# Controllerv2.net
KiCad netlist of a schematic drawn in EAGLE
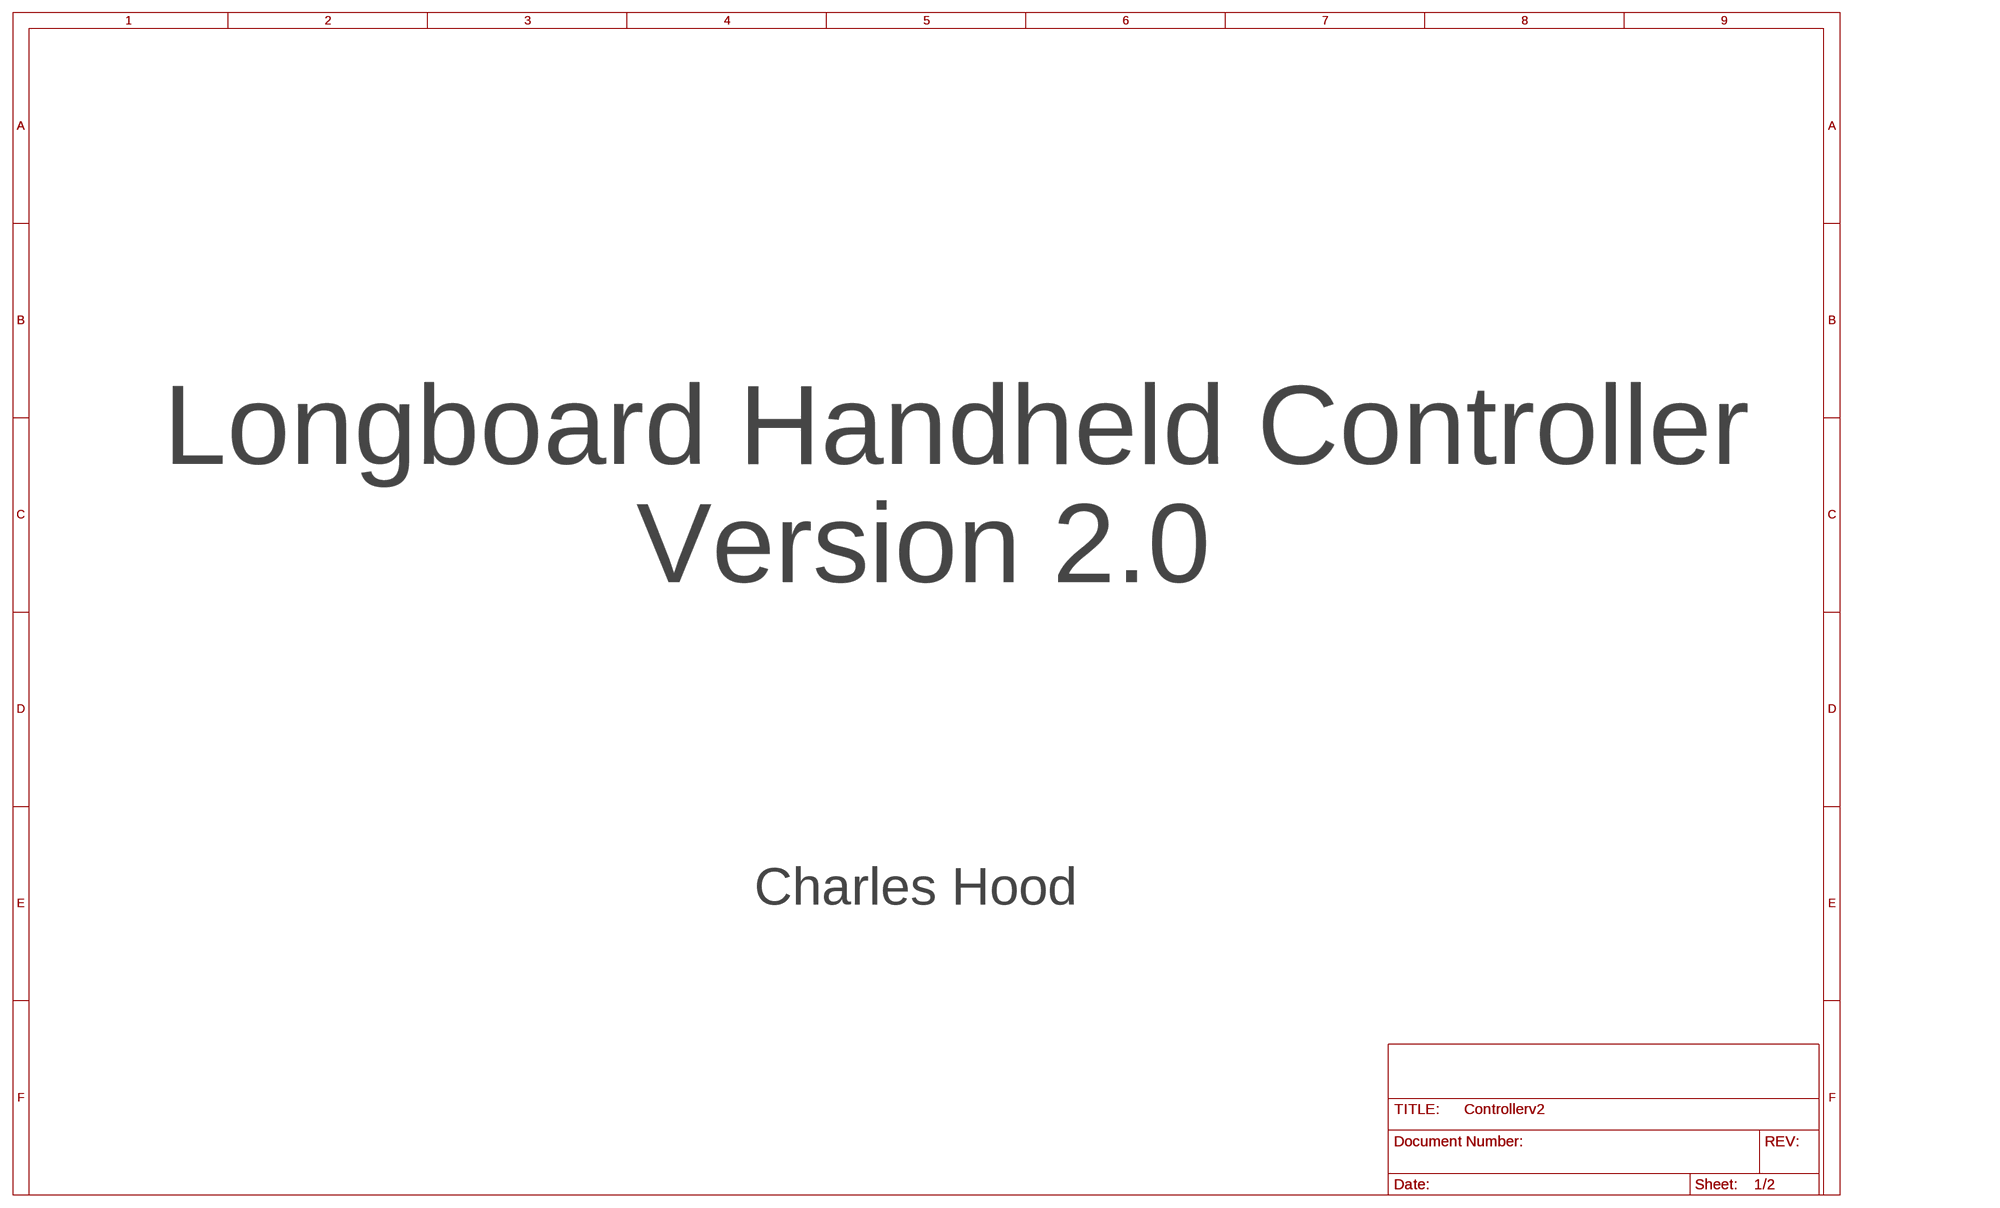
[diagram p0: schematic, sheet 1]
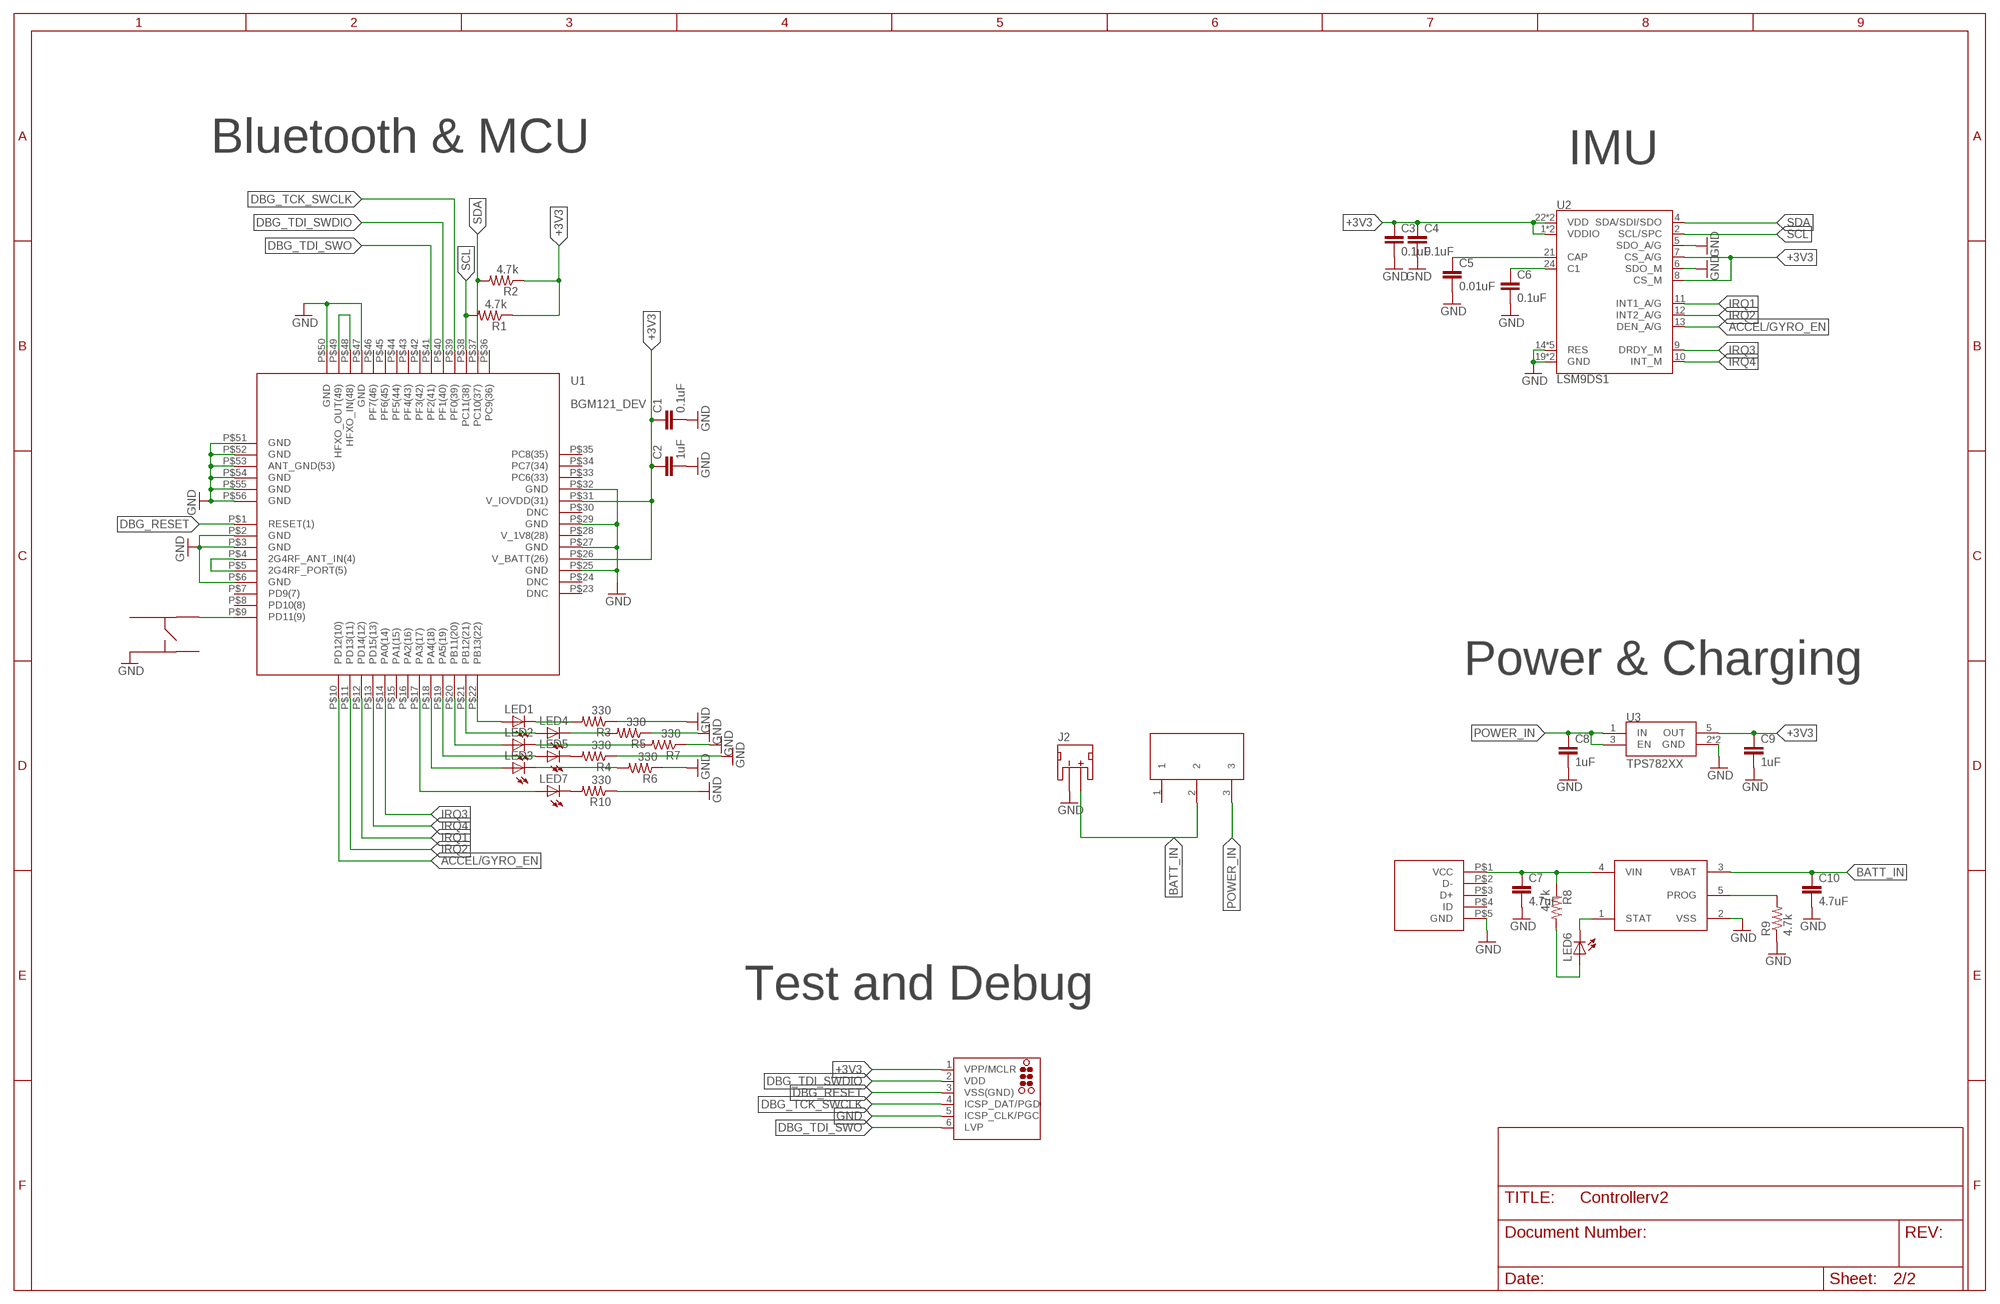
[diagram p1: schematic, sheet 2]

(export (version "E")
  (design (tool "Eeschema 10.0.6"))
  (components
    (comp (ref "C1")
      (value "0.1uF")
      (footprint "eagle-import:C0201")
      (libsource (lib "eagle-import") (part "C-EUC0201"))
    )
    (comp (ref "C2")
      (value "1uF")
      (footprint "eagle-import:C0201")
      (libsource (lib "eagle-import") (part "C-EUC0201"))
    )
    (comp (ref "C3")
      (value "0.1uF")
      (footprint "eagle-import:C0201")
      (libsource (lib "eagle-import") (part "C-EUC0201"))
    )
    (comp (ref "C4")
      (value "0.1uF")
      (footprint "eagle-import:C0201")
      (libsource (lib "eagle-import") (part "C-EUC0201"))
    )
    (comp (ref "C5")
      (value "0.01uF")
      (footprint "eagle-import:C0201")
      (libsource (lib "eagle-import") (part "C-EUC0201"))
    )
    (comp (ref "C6")
      (value "0.1uF")
      (footprint "eagle-import:C0201")
      (libsource (lib "eagle-import") (part "C-EUC0201"))
    )
    (comp (ref "C7")
      (value "4.7uF")
      (footprint "eagle-import:C0402")
      (libsource (lib "eagle-import") (part "C-EUC0402"))
    )
    (comp (ref "C8")
      (value "1uF")
      (footprint "eagle-import:C0201")
      (libsource (lib "eagle-import") (part "C-EUC0201"))
    )
    (comp (ref "C9")
      (value "1uF")
      (footprint "eagle-import:C0201")
      (libsource (lib "eagle-import") (part "C-EUC0201"))
    )
    (comp (ref "C10")
      (value "4.7uF")
      (footprint "eagle-import:C0402")
      (libsource (lib "eagle-import") (part "C-EUC0402"))
    )
    (comp (ref "J1")
      (value "MICRO_USB")
      (footprint "eagle-import:MOLEX_USB")
      (libsource (lib "eagle-import") (part "MICRO_USB"))
    )
    (comp (ref "J2")
      (value "JST_2MM_MALE")
      (footprint "eagle-import:JST-2-SMD")
      (libsource (lib "eagle-import") (part "JST_2MM_MALE"))
    )
    (comp (ref "J3")
      (value "TC2030-MCP-NL")
      (footprint "eagle-import:TC2030-MCP-NL")
      (libsource (lib "eagle-import") (part "TC2030-MCP-NL"))
    )
    (comp (ref "LED1")
      (value "LEDCHIP-LED0603")
      (footprint "eagle-import:CHIP-LED0603")
      (libsource (lib "eagle-import") (part "LEDCHIP-LED0603"))
    )
    (comp (ref "LED2")
      (value "LEDCHIP-LED0603")
      (footprint "eagle-import:CHIP-LED0603")
      (libsource (lib "eagle-import") (part "LEDCHIP-LED0603"))
    )
    (comp (ref "LED3")
      (value "LEDCHIP-LED0603")
      (footprint "eagle-import:CHIP-LED0603")
      (libsource (lib "eagle-import") (part "LEDCHIP-LED0603"))
    )
    (comp (ref "LED4")
      (value "LEDCHIP-LED0603")
      (footprint "eagle-import:CHIP-LED0603")
      (libsource (lib "eagle-import") (part "LEDCHIP-LED0603"))
    )
    (comp (ref "LED5")
      (value "LEDCHIP-LED0603")
      (footprint "eagle-import:CHIP-LED0603")
      (libsource (lib "eagle-import") (part "LEDCHIP-LED0603"))
    )
    (comp (ref "LED6")
      (value "LEDCHIP-LED0603")
      (footprint "eagle-import:CHIP-LED0603")
      (libsource (lib "eagle-import") (part "LEDCHIP-LED0603"))
    )
    (comp (ref "LED7")
      (value "LEDCHIP-LED0603")
      (footprint "eagle-import:CHIP-LED0603")
      (libsource (lib "eagle-import") (part "LEDCHIP-LED0603"))
    )
    (comp (ref "R1")
      (value "4.7k")
      (footprint "eagle-import:R0201")
      (libsource (lib "eagle-import") (part "R-US_R0201"))
    )
    (comp (ref "R2")
      (value "4.7k")
      (footprint "eagle-import:R0201")
      (libsource (lib "eagle-import") (part "R-US_R0201"))
    )
    (comp (ref "R3")
      (value "330")
      (footprint "eagle-import:R0201")
      (libsource (lib "eagle-import") (part "R-US_R0201"))
    )
    (comp (ref "R4")
      (value "330")
      (footprint "eagle-import:R0201")
      (libsource (lib "eagle-import") (part "R-US_R0201"))
    )
    (comp (ref "R5")
      (value "330")
      (footprint "eagle-import:R0201")
      (libsource (lib "eagle-import") (part "R-US_R0201"))
    )
    (comp (ref "R6")
      (value "330")
      (footprint "eagle-import:R0201")
      (libsource (lib "eagle-import") (part "R-US_R0201"))
    )
    (comp (ref "R7")
      (value "330")
      (footprint "eagle-import:R0201")
      (libsource (lib "eagle-import") (part "R-US_R0201"))
    )
    (comp (ref "R8")
      (value "4.7k")
      (footprint "eagle-import:R0201")
      (libsource (lib "eagle-import") (part "R-US_R0201"))
    )
    (comp (ref "R9")
      (value "4.7k")
      (footprint "eagle-import:R0201")
      (libsource (lib "eagle-import") (part "R-US_R0201"))
    )
    (comp (ref "R10")
      (value "330")
      (footprint "eagle-import:R0201")
      (libsource (lib "eagle-import") (part "R-US_R0201"))
    )
    (comp (ref "S1")
      (value "KMR731NG")
      (footprint "eagle-import:KMR731NG")
      (libsource (lib "eagle-import") (part "KMR731NG"))
    )
    (comp (ref "U$1")
      (value "SPDT_THRU")
      (footprint "eagle-import:SPDT_THRU")
      (libsource (lib "eagle-import") (part "SPDT_THRU"))
    )
    (comp (ref "U1")
      (value "BGM121_DEV")
      (footprint "eagle-import:BGM121_PAC")
      (libsource (lib "eagle-import") (part "BGM121_DEV"))
    )
    (comp (ref "U2")
      (value "LSM9DS1")
      (footprint "eagle-import:LGA24-8X4")
      (libsource (lib "eagle-import") (part "LSM9DS1"))
    )
    (comp (ref "U3")
      (value "TPS782XX")
      (footprint "eagle-import:SOT23-5L")
      (libsource (lib "eagle-import") (part "TPS782XX"))
    )
    (comp (ref "U4")
      (value "MCP73831")
      (footprint "eagle-import:SOT23-5L")
      (libsource (lib "eagle-import") (part "MCP73831"))
    )
  )
  (nets
    (net (code "1") (name "+3V3") (class "Default")
      (node (ref "C1") (pin "1") (pinfunction "1_1") (pintype "passive"))
      (node (ref "C2") (pin "1") (pinfunction "1_1") (pintype "passive"))
      (node (ref "C3") (pin "1") (pinfunction "1_1") (pintype "passive"))
      (node (ref "C4") (pin "1") (pinfunction "1_1") (pintype "passive"))
      (node (ref "C9") (pin "1") (pinfunction "1_1") (pintype "passive"))
      (node (ref "J3") (pin "1") (pinfunction "VPP/MCLR_1") (pintype "passive"))
      (node (ref "R1") (pin "1") (pinfunction "1_1") (pintype "passive"))
      (node (ref "R2") (pin "1") (pinfunction "1_1") (pintype "passive"))
      (node (ref "U1") (pin "P$26") (pinfunction "V_BATT(26)_P$26") (pintype "power_in"))
      (node (ref "U1") (pin "P$31") (pinfunction "V_IOVDD(31)_P$31") (pintype "power_in"))
      (node (ref "U2") (pin "1") (pinfunction "VDDIO_1") (pintype "bidirectional"))
      (node (ref "U2") (pin "22") (pinfunction "VDD_22") (pintype "bidirectional"))
      (node (ref "U2") (pin "23") (pinfunction "VDD_23") (pintype "bidirectional"))
      (node (ref "U2") (pin "3") (pinfunction "VDDIO_3") (pintype "bidirectional"))
      (node (ref "U2") (pin "7") (pinfunction "CS_A/G_7") (pintype "bidirectional"))
      (node (ref "U2") (pin "8") (pinfunction "CS_M_8") (pintype "bidirectional"))
      (node (ref "U3") (pin "5") (pinfunction "OUT_5") (pintype "bidirectional"))
    )
    (net (code "2") (name "ACCEL{slash}GYRO_EN") (class "Default")
      (node (ref "U1") (pin "P$10") (pinfunction "PD12(10)_P$10") (pintype "bidirectional"))
      (node (ref "U2") (pin "13") (pinfunction "DEN_A/G_13") (pintype "bidirectional"))
    )
    (net (code "3") (name "BATT_IN") (class "Default")
      (node (ref "C10") (pin "1") (pinfunction "1_1") (pintype "passive"))
      (node (ref "J2") (pin "2") (pinfunction "+_2") (pintype "bidirectional"))
      (node (ref "U$1") (pin "2") (pinfunction "2_2") (pintype "bidirectional"))
      (node (ref "U4") (pin "3") (pinfunction "VBAT_3") (pintype "bidirectional"))
    )
    (net (code "4") (name "DBG_RESET") (class "Default")
      (node (ref "J3") (pin "3") (pinfunction "VSS(GND)_3") (pintype "power_in"))
      (node (ref "U1") (pin "P$1") (pinfunction "RESET(1)_P$1") (pintype "input"))
    )
    (net (code "5") (name "DBG_TCK_SWCLK") (class "Default")
      (node (ref "J3") (pin "4") (pinfunction "ICSP_DAT/PGD_4") (pintype "bidirectional"))
      (node (ref "U1") (pin "P$39") (pinfunction "PF0(39)_P$39") (pintype "bidirectional"))
    )
    (net (code "6") (name "DBG_TDI_SWDIO") (class "Default")
      (node (ref "J3") (pin "2") (pinfunction "VDD_2") (pintype "power_in"))
      (node (ref "U1") (pin "P$40") (pinfunction "PF1(40)_P$40") (pintype "bidirectional"))
    )
    (net (code "7") (name "DBG_TDI_SWO") (class "Default")
      (node (ref "J3") (pin "6") (pinfunction "LVP_6") (pintype "bidirectional"))
      (node (ref "U1") (pin "P$41") (pinfunction "PF2(41)_P$41") (pintype "bidirectional"))
    )
    (net (code "8") (name "GND") (class "Default")
      (node (ref "C1") (pin "2") (pinfunction "2_2") (pintype "passive"))
      (node (ref "C10") (pin "2") (pinfunction "2_2") (pintype "passive"))
      (node (ref "C2") (pin "2") (pinfunction "2_2") (pintype "passive"))
      (node (ref "C3") (pin "2") (pinfunction "2_2") (pintype "passive"))
      (node (ref "C4") (pin "2") (pinfunction "2_2") (pintype "passive"))
      (node (ref "C5") (pin "2") (pinfunction "2_2") (pintype "passive"))
      (node (ref "C6") (pin "2") (pinfunction "2_2") (pintype "passive"))
      (node (ref "C7") (pin "2") (pinfunction "2_2") (pintype "passive"))
      (node (ref "C8") (pin "2") (pinfunction "2_2") (pintype "passive"))
      (node (ref "C9") (pin "2") (pinfunction "2_2") (pintype "passive"))
      (node (ref "J1") (pin "P$5") (pinfunction "GND_P$5") (pintype "bidirectional"))
      (node (ref "J2") (pin "1") (pinfunction "-_1") (pintype "bidirectional"))
      (node (ref "J3") (pin "5") (pinfunction "ICSP_CLK/PGC_5") (pintype "output"))
      (node (ref "R10") (pin "1") (pinfunction "1_1") (pintype "passive"))
      (node (ref "R3") (pin "1") (pinfunction "1_1") (pintype "passive"))
      (node (ref "R4") (pin "1") (pinfunction "1_1") (pintype "passive"))
      (node (ref "R5") (pin "1") (pinfunction "1_1") (pintype "passive"))
      (node (ref "R6") (pin "1") (pinfunction "1_1") (pintype "passive"))
      (node (ref "R7") (pin "1") (pinfunction "1_1") (pintype "passive"))
      (node (ref "R9") (pin "1") (pinfunction "1_1") (pintype "passive"))
      (node (ref "S1") (pin "P$4") (pinfunction "P$4_P$4") (pintype "bidirectional"))
      (node (ref "U1") (pin "P$2") (pinfunction "GND_P$2") (pintype "power_in"))
      (node (ref "U1") (pin "P$25") (pinfunction "GND_P$25") (pintype "power_in"))
      (node (ref "U1") (pin "P$27") (pinfunction "GND_P$27") (pintype "power_in"))
      (node (ref "U1") (pin "P$29") (pinfunction "GND_P$29") (pintype "power_in"))
      (node (ref "U1") (pin "P$3") (pinfunction "GND_P$3") (pintype "power_in"))
      (node (ref "U1") (pin "P$32") (pinfunction "GND_P$32") (pintype "power_in"))
      (node (ref "U1") (pin "P$47") (pinfunction "GND_P$47") (pintype "power_in"))
      (node (ref "U1") (pin "P$50") (pinfunction "GND_P$50") (pintype "power_in"))
      (node (ref "U1") (pin "P$51") (pinfunction "GND_P$51") (pintype "power_in"))
      (node (ref "U1") (pin "P$52") (pinfunction "GND_P$52") (pintype "power_in"))
      (node (ref "U1") (pin "P$53") (pinfunction "ANT_GND(53)_P$53") (pintype "power_in"))
      (node (ref "U1") (pin "P$54") (pinfunction "GND_P$54") (pintype "power_in"))
      (node (ref "U1") (pin "P$55") (pinfunction "GND_P$55") (pintype "power_in"))
      (node (ref "U1") (pin "P$56") (pinfunction "GND_P$56") (pintype "power_in"))
      (node (ref "U1") (pin "P$6") (pinfunction "GND_P$6") (pintype "power_in"))
      (node (ref "U2") (pin "14") (pinfunction "RES_14") (pintype "bidirectional"))
      (node (ref "U2") (pin "15") (pinfunction "RES_15") (pintype "bidirectional"))
      (node (ref "U2") (pin "16") (pinfunction "RES_16") (pintype "bidirectional"))
      (node (ref "U2") (pin "17") (pinfunction "RES_17") (pintype "bidirectional"))
      (node (ref "U2") (pin "18") (pinfunction "RES_18") (pintype "bidirectional"))
      (node (ref "U2") (pin "19") (pinfunction "GND_19") (pintype "bidirectional"))
      (node (ref "U2") (pin "20") (pinfunction "GND_20") (pintype "bidirectional"))
      (node (ref "U2") (pin "5") (pinfunction "SDO_A/G_5") (pintype "bidirectional"))
      (node (ref "U2") (pin "6") (pinfunction "SDO_M_6") (pintype "bidirectional"))
      (node (ref "U3") (pin "2") (pinfunction "GND_2") (pintype "bidirectional"))
      (node (ref "U3") (pin "4") (pinfunction "GND_4") (pintype "bidirectional"))
      (node (ref "U4") (pin "2") (pinfunction "VSS_2") (pintype "bidirectional"))
    )
    (net (code "9") (name "IRQ1") (class "Default")
      (node (ref "U1") (pin "P$12") (pinfunction "PD14(12)_P$12") (pintype "bidirectional"))
      (node (ref "U2") (pin "11") (pinfunction "INT1_A/G_11") (pintype "bidirectional"))
    )
    (net (code "10") (name "IRQ2") (class "Default")
      (node (ref "U1") (pin "P$11") (pinfunction "PD13(11)_P$11") (pintype "bidirectional"))
      (node (ref "U2") (pin "12") (pinfunction "INT2_A/G_12") (pintype "bidirectional"))
    )
    (net (code "11") (name "IRQ3") (class "Default")
      (node (ref "U1") (pin "P$14") (pinfunction "PA0(14)_P$14") (pintype "bidirectional"))
      (node (ref "U2") (pin "9") (pinfunction "DRDY_M_9") (pintype "bidirectional"))
    )
    (net (code "12") (name "IRQ4") (class "Default")
      (node (ref "U1") (pin "P$13") (pinfunction "PD15(13)_P$13") (pintype "bidirectional"))
      (node (ref "U2") (pin "10") (pinfunction "INT_M_10") (pintype "bidirectional"))
    )
    (net (code "13") (name "Net-(J1-VCC)") (class "Default")
      (node (ref "C7") (pin "1") (pinfunction "1_1") (pintype "passive"))
      (node (ref "J1") (pin "P$1") (pinfunction "VCC_P$1") (pintype "bidirectional"))
      (node (ref "R8") (pin "1") (pinfunction "1_1") (pintype "passive"))
      (node (ref "U4") (pin "4") (pinfunction "VIN_4") (pintype "bidirectional"))
    )
    (net (code "14") (name "Net-(LED1-PadC)") (class "Default")
      (node (ref "LED1") (pin "C") (pinfunction "C_C") (pintype "passive"))
      (node (ref "R3") (pin "2") (pinfunction "2_2") (pintype "passive"))
    )
    (net (code "15") (name "Net-(LED2-PadC)") (class "Default")
      (node (ref "LED2") (pin "C") (pinfunction "C_C") (pintype "passive"))
      (node (ref "R7") (pin "2") (pinfunction "2_2") (pintype "passive"))
    )
    (net (code "16") (name "Net-(LED3-PadC)") (class "Default")
      (node (ref "LED3") (pin "C") (pinfunction "C_C") (pintype "passive"))
      (node (ref "R6") (pin "2") (pinfunction "2_2") (pintype "passive"))
    )
    (net (code "17") (name "Net-(LED4-PadC)") (class "Default")
      (node (ref "LED4") (pin "C") (pinfunction "C_C") (pintype "passive"))
      (node (ref "R5") (pin "2") (pinfunction "2_2") (pintype "passive"))
    )
    (net (code "18") (name "Net-(LED5-PadC)") (class "Default")
      (node (ref "LED5") (pin "C") (pinfunction "C_C") (pintype "passive"))
      (node (ref "R4") (pin "2") (pinfunction "2_2") (pintype "passive"))
    )
    (net (code "19") (name "Net-(LED6-PadA)") (class "Default")
      (node (ref "LED6") (pin "A") (pinfunction "A_A") (pintype "passive"))
      (node (ref "R8") (pin "2") (pinfunction "2_2") (pintype "passive"))
    )
    (net (code "20") (name "Net-(LED7-PadC)") (class "Default")
      (node (ref "LED7") (pin "C") (pinfunction "C_C") (pintype "passive"))
      (node (ref "R10") (pin "2") (pinfunction "2_2") (pintype "passive"))
    )
    (net (code "21") (name "Net-(U1-2G4RF_ANT_IN(4))") (class "Default")
      (node (ref "U1") (pin "P$4") (pinfunction "2G4RF_ANT_IN(4)_P$4") (pintype "input"))
      (node (ref "U1") (pin "P$5") (pinfunction "2G4RF_PORT(5)_P$5") (pintype "input"))
    )
    (net (code "22") (name "Net-(U1-HFXO_IN(48))") (class "Default")
      (node (ref "U1") (pin "P$48") (pinfunction "HFXO_IN(48)_P$48") (pintype "input"))
      (node (ref "U1") (pin "P$49") (pinfunction "HFXO_OUT(49)_P$49") (pintype "output"))
    )
    (net (code "23") (name "Net-(U1-PA3(17))") (class "Default")
      (node (ref "LED7") (pin "A") (pinfunction "A_A") (pintype "passive"))
      (node (ref "U1") (pin "P$17") (pinfunction "PA3(17)_P$17") (pintype "bidirectional"))
    )
    (net (code "24") (name "Net-(U1-PA4(18))") (class "Default")
      (node (ref "LED3") (pin "A") (pinfunction "A_A") (pintype "passive"))
      (node (ref "U1") (pin "P$18") (pinfunction "PA4(18)_P$18") (pintype "bidirectional"))
    )
    (net (code "25") (name "Net-(U1-PA5(19))") (class "Default")
      (node (ref "LED5") (pin "A") (pinfunction "A_A") (pintype "passive"))
      (node (ref "U1") (pin "P$19") (pinfunction "PA5(19)_P$19") (pintype "bidirectional"))
    )
    (net (code "26") (name "Net-(U1-PB11(20))") (class "Default")
      (node (ref "LED2") (pin "A") (pinfunction "A_A") (pintype "passive"))
      (node (ref "U1") (pin "P$20") (pinfunction "PB11(20)_P$20") (pintype "bidirectional"))
    )
    (net (code "27") (name "Net-(U1-PB12(21))") (class "Default")
      (node (ref "LED4") (pin "A") (pinfunction "A_A") (pintype "passive"))
      (node (ref "U1") (pin "P$21") (pinfunction "PB12(21)_P$21") (pintype "bidirectional"))
    )
    (net (code "28") (name "Net-(U1-PB13(22))") (class "Default")
      (node (ref "LED1") (pin "A") (pinfunction "A_A") (pintype "passive"))
      (node (ref "U1") (pin "P$22") (pinfunction "PB13(22)_P$22") (pintype "bidirectional"))
    )
    (net (code "29") (name "Net-(U1-PD11(9))") (class "Default")
      (node (ref "S1") (pin "P$2") (pinfunction "P$2_P$2") (pintype "bidirectional"))
      (node (ref "U1") (pin "P$9") (pinfunction "PD11(9)_P$9") (pintype "bidirectional"))
    )
    (net (code "30") (name "Net-(U2-C1)") (class "Default")
      (node (ref "C6") (pin "1") (pinfunction "1_1") (pintype "passive"))
      (node (ref "U2") (pin "24") (pinfunction "C1_24") (pintype "bidirectional"))
    )
    (net (code "31") (name "Net-(U2-CAP)") (class "Default")
      (node (ref "C5") (pin "1") (pinfunction "1_1") (pintype "passive"))
      (node (ref "U2") (pin "21") (pinfunction "CAP_21") (pintype "bidirectional"))
    )
    (net (code "32") (name "Net-(U4-PROG)") (class "Default")
      (node (ref "R9") (pin "2") (pinfunction "2_2") (pintype "passive"))
      (node (ref "U4") (pin "5") (pinfunction "PROG_5") (pintype "bidirectional"))
    )
    (net (code "33") (name "Net-(U4-STAT)") (class "Default")
      (node (ref "LED6") (pin "C") (pinfunction "C_C") (pintype "passive"))
      (node (ref "U4") (pin "1") (pinfunction "STAT_1") (pintype "bidirectional"))
    )
    (net (code "34") (name "POWER_IN") (class "Default")
      (node (ref "C8") (pin "1") (pinfunction "1_1") (pintype "passive"))
      (node (ref "U$1") (pin "3") (pinfunction "3_3") (pintype "bidirectional"))
      (node (ref "U3") (pin "1") (pinfunction "IN_1") (pintype "bidirectional"))
      (node (ref "U3") (pin "3") (pinfunction "EN_3") (pintype "bidirectional"))
    )
    (net (code "35") (name "SCL") (class "Default")
      (node (ref "R1") (pin "2") (pinfunction "2_2") (pintype "passive"))
      (node (ref "U1") (pin "P$38") (pinfunction "PC11(38)_P$38") (pintype "bidirectional"))
      (node (ref "U2") (pin "2") (pinfunction "SCL/SPC_2") (pintype "bidirectional"))
    )
    (net (code "36") (name "SDA") (class "Default")
      (node (ref "R2") (pin "2") (pinfunction "2_2") (pintype "passive"))
      (node (ref "U1") (pin "P$37") (pinfunction "PC10(37)_P$37") (pintype "bidirectional"))
      (node (ref "U2") (pin "4") (pinfunction "SDA/SDI/SDO_4") (pintype "bidirectional"))
    )
    (net (code "37") (name "V_1V8(28)") (class "Default")
      (node (ref "U1") (pin "P$28") (pinfunction "V_1V8(28)_P$28") (pintype "power_in"))
    )
    (net (code "38") (name "unconnected-(J1-D+-PadP$3)") (class "Default")
      (node (ref "J1") (pin "P$3") (pinfunction "D+_P$3") (pintype "bidirectional"))
    )
    (net (code "39") (name "unconnected-(J1-D--PadP$2)") (class "Default")
      (node (ref "J1") (pin "P$2") (pinfunction "D-_P$2") (pintype "bidirectional"))
    )
    (net (code "40") (name "unconnected-(J1-ID-PadP$4)") (class "Default")
      (node (ref "J1") (pin "P$4") (pinfunction "ID_P$4") (pintype "bidirectional"))
    )
    (net (code "41") (name "unconnected-(J2-PAD1-PadNC1)") (class "Default")
      (node (ref "J2") (pin "NC1") (pinfunction "PAD1_NC1") (pintype "bidirectional"))
    )
    (net (code "42") (name "unconnected-(J2-PAD2-PadNC2)") (class "Default")
      (node (ref "J2") (pin "NC2") (pinfunction "PAD2_NC2") (pintype "bidirectional"))
    )
    (net (code "43") (name "unconnected-(S1-PadP$1)") (class "Default")
      (node (ref "S1") (pin "P$1") (pinfunction "P$1_P$1") (pintype "bidirectional"))
    )
    (net (code "44") (name "unconnected-(S1-PadP$3)") (class "Default")
      (node (ref "S1") (pin "P$3") (pinfunction "P$3_P$3") (pintype "bidirectional"))
    )
    (net (code "45") (name "unconnected-(U$1-Pad1)") (class "Default")
      (node (ref "U$1") (pin "1") (pinfunction "1_1") (pintype "bidirectional"))
    )
    (net (code "46") (name "unconnected-(U1-DNC-PadP$23)") (class "Default")
      (node (ref "U1") (pin "P$23") (pinfunction "DNC_P$23") (pintype "no_connect"))
    )
    (net (code "47") (name "unconnected-(U1-DNC-PadP$24)") (class "Default")
      (node (ref "U1") (pin "P$24") (pinfunction "DNC_P$24") (pintype "no_connect"))
    )
    (net (code "48") (name "unconnected-(U1-DNC-PadP$30)") (class "Default")
      (node (ref "U1") (pin "P$30") (pinfunction "DNC_P$30") (pintype "no_connect"))
    )
    (net (code "49") (name "unconnected-(U1-PA1(15)-PadP$15)") (class "Default")
      (node (ref "U1") (pin "P$15") (pinfunction "PA1(15)_P$15") (pintype "bidirectional"))
    )
    (net (code "50") (name "unconnected-(U1-PA2(16)-PadP$16)") (class "Default")
      (node (ref "U1") (pin "P$16") (pinfunction "PA2(16)_P$16") (pintype "bidirectional"))
    )
    (net (code "51") (name "unconnected-(U1-PC6(33)-PadP$33)") (class "Default")
      (node (ref "U1") (pin "P$33") (pinfunction "PC6(33)_P$33") (pintype "bidirectional"))
    )
    (net (code "52") (name "unconnected-(U1-PC7(34)-PadP$34)") (class "Default")
      (node (ref "U1") (pin "P$34") (pinfunction "PC7(34)_P$34") (pintype "bidirectional"))
    )
    (net (code "53") (name "unconnected-(U1-PC8(35)-PadP$35)") (class "Default")
      (node (ref "U1") (pin "P$35") (pinfunction "PC8(35)_P$35") (pintype "bidirectional"))
    )
    (net (code "54") (name "unconnected-(U1-PC9(36)-PadP$36)") (class "Default")
      (node (ref "U1") (pin "P$36") (pinfunction "PC9(36)_P$36") (pintype "bidirectional"))
    )
    (net (code "55") (name "unconnected-(U1-PD9(7)-PadP$7)") (class "Default")
      (node (ref "U1") (pin "P$7") (pinfunction "PD9(7)_P$7") (pintype "bidirectional"))
    )
    (net (code "56") (name "unconnected-(U1-PD10(8)-PadP$8)") (class "Default")
      (node (ref "U1") (pin "P$8") (pinfunction "PD10(8)_P$8") (pintype "bidirectional"))
    )
    (net (code "57") (name "unconnected-(U1-PF3(42)-PadP$42)") (class "Default")
      (node (ref "U1") (pin "P$42") (pinfunction "PF3(42)_P$42") (pintype "bidirectional"))
    )
    (net (code "58") (name "unconnected-(U1-PF4(43)-PadP$43)") (class "Default")
      (node (ref "U1") (pin "P$43") (pinfunction "PF4(43)_P$43") (pintype "bidirectional"))
    )
    (net (code "59") (name "unconnected-(U1-PF5(44)-PadP$44)") (class "Default")
      (node (ref "U1") (pin "P$44") (pinfunction "PF5(44)_P$44") (pintype "bidirectional"))
    )
    (net (code "60") (name "unconnected-(U1-PF6(45)-PadP$45)") (class "Default")
      (node (ref "U1") (pin "P$45") (pinfunction "PF6(45)_P$45") (pintype "bidirectional"))
    )
    (net (code "61") (name "unconnected-(U1-PF7(46)-PadP$46)") (class "Default")
      (node (ref "U1") (pin "P$46") (pinfunction "PF7(46)_P$46") (pintype "bidirectional"))
    )
  )
)
